# PowerSupply.net
KiCad netlist of a schematic drawn in EAGLE
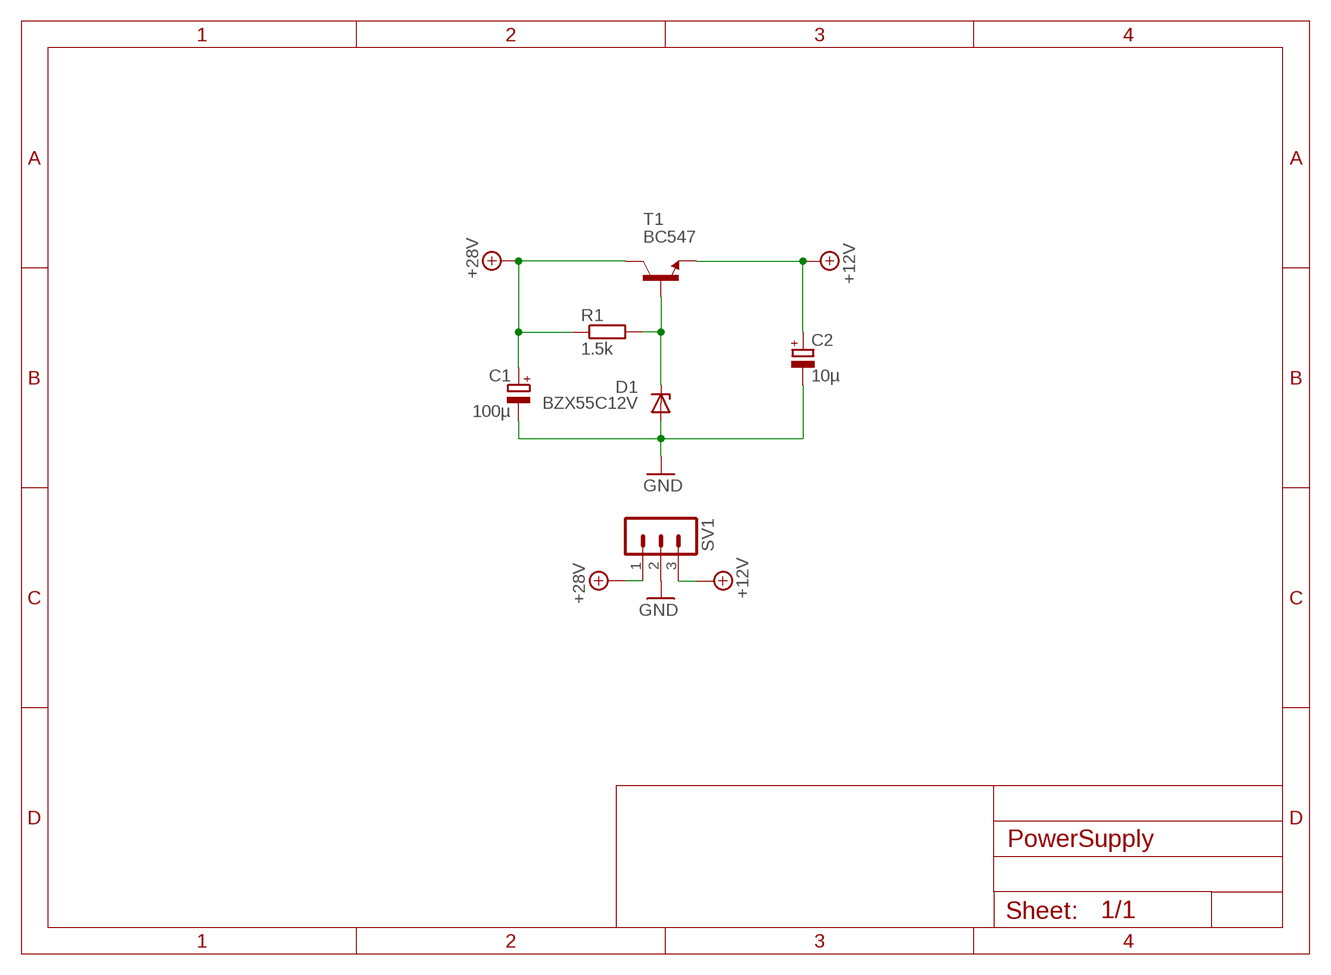
[diagram p0: schematic, sheet 1]

(export (version "E")
  (design (tool "Eeschema 10.0.6"))
  (components
    (comp (ref "C1")
      (value "100µ")
      (footprint "eagle-import:E5-10,5")
      (libsource (lib "eagle-import") (part "CPOL-EUE5-10.5"))
    )
    (comp (ref "C2")
      (value "10µ")
      (footprint "eagle-import:E5-8,5")
      (libsource (lib "eagle-import") (part "CPOL-EUE5-8.5"))
    )
    (comp (ref "D1")
      (value "BZX55C12V")
      (footprint "eagle-import:DO35Z10")
      (libsource (lib "eagle-import") (part "BZX55"))
    )
    (comp (ref "R1")
      (value "1.5k")
      (footprint "eagle-import:0309_12")
      (libsource (lib "eagle-import") (part "R-EU_0309/12"))
    )
    (comp (ref "SV1")
      (value "MA03-1")
      (footprint "eagle-import:MA03-1")
      (libsource (lib "eagle-import") (part "MA03-1"))
    )
    (comp (ref "T1")
      (value "BC547")
      (footprint "eagle-import:TO92")
      (libsource (lib "eagle-import") (part "BC547"))
    )
  )
  (nets
    (net (code "1") (name "+12V") (class "Default")
      (node (ref "C2") (pin "+") (pinfunction "+_+") (pintype "passive"))
      (node (ref "SV1") (pin "3") (pinfunction "3_3") (pintype "passive"))
      (node (ref "T1") (pin "1") (pinfunction "E_1") (pintype "passive"))
    )
    (net (code "2") (name "+28V") (class "Default")
      (node (ref "C1") (pin "+") (pinfunction "+_+") (pintype "passive"))
      (node (ref "R1") (pin "1") (pinfunction "1_1") (pintype "passive"))
      (node (ref "SV1") (pin "1") (pinfunction "1_1") (pintype "passive"))
      (node (ref "T1") (pin "3") (pinfunction "C_3") (pintype "passive"))
    )
    (net (code "3") (name "GND") (class "Default")
      (node (ref "C1") (pin "-") (pinfunction "-_-") (pintype "passive"))
      (node (ref "C2") (pin "-") (pinfunction "-_-") (pintype "passive"))
      (node (ref "D1") (pin "A") (pinfunction "A_A") (pintype "passive"))
      (node (ref "SV1") (pin "2") (pinfunction "2_2") (pintype "passive"))
    )
    (net (code "4") (name "Net-(T1-B)") (class "Default")
      (node (ref "D1") (pin "C") (pinfunction "C_C") (pintype "passive"))
      (node (ref "R1") (pin "2") (pinfunction "2_2") (pintype "passive"))
      (node (ref "T1") (pin "2") (pinfunction "B_2") (pintype "passive"))
    )
  )
)
